# Sheet1TASK1.net
KiCad netlist of a schematic drawn in Altium Designer
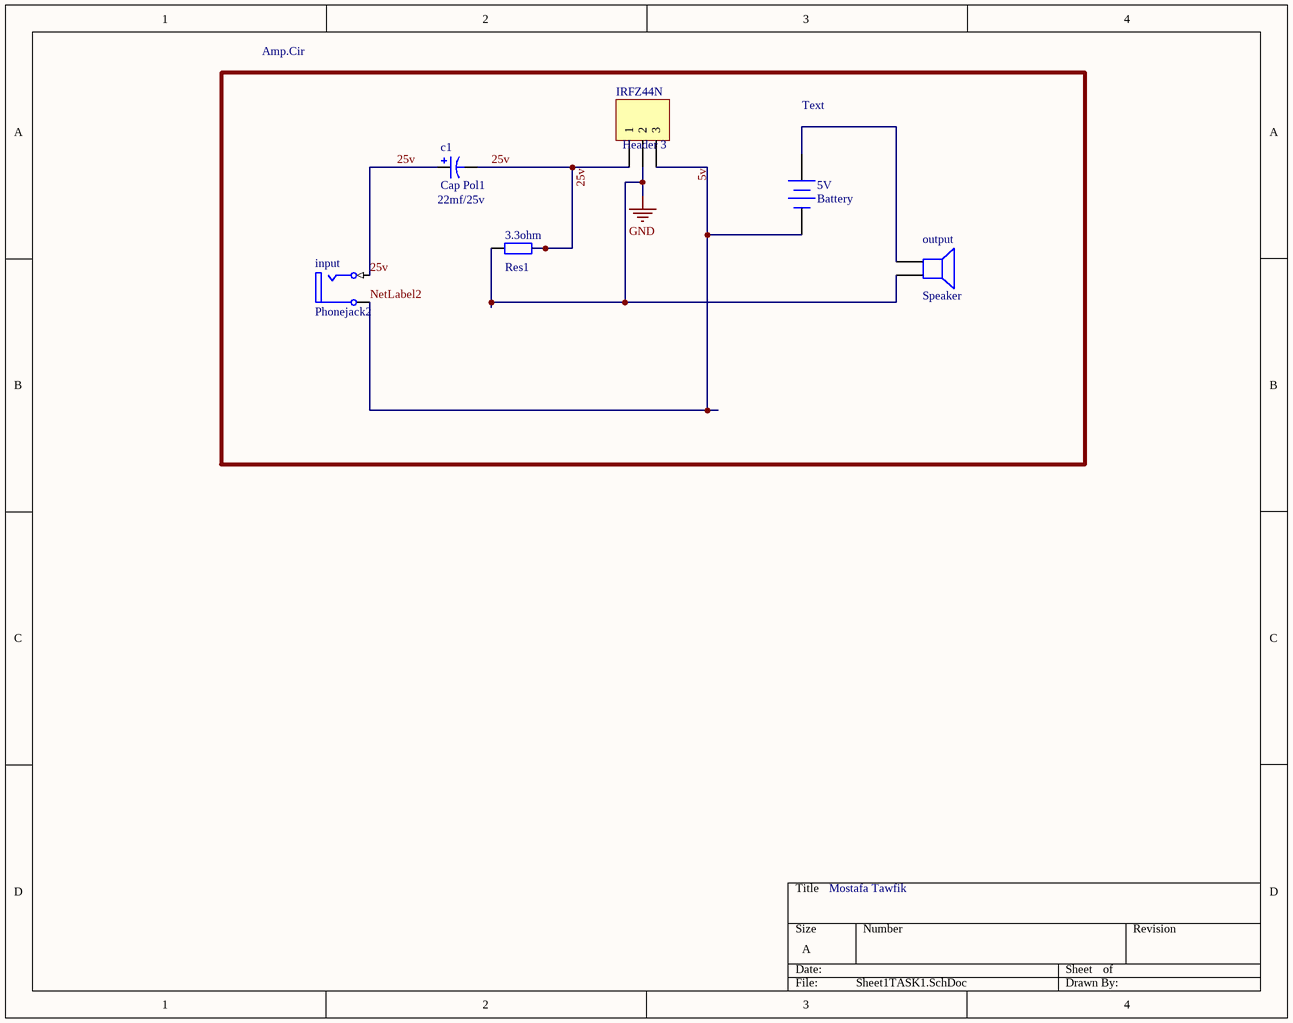
[diagram p0: Sheet1TASK1.SchDoc]

(export (version "E")
  (design (tool "Eeschema 10.0.6"))
  (components
    (comp (ref "3.3ohm")
      (value "Res1")
      (footprint "AXIAL-0.4")
      (description "Resistor")
      (fields (field (name "PUBLISHER") "Altium Limited"))
      (libsource (lib "Miscellaneous Devices") (part "Res2"))
    )
    (comp (ref "5V")
      (value "Battery")
      (footprint "BAT-2")
      (description "Multicell Battery")
      (fields (field (name "PUBLISHER") "Altium Limited"))
      (libsource (lib "Miscellaneous Devices") (part "Battery"))
    )
    (comp (ref "c1")
      (value "Cap Pol1")
      (footprint "RB7.6-15")
      (description "Polarized Capacitor (Radial)")
      (fields (field (name "ALTIUM_VALUE") "22mf/25v") (field (name "PUBLISHER") "Altium Limited"))
      (libsource (lib "Miscellaneous Devices") (part "Cap Pol1"))
    )
    (comp (ref "input")
      (value "Phonejack2")
      (footprint "JACK/6-V2")
      (description "Jack Socket, 1/4\" [6.5mm], Thru-Hole, Vertical, 2-Conductor Open Circuit")
      (fields (field (name "PUBLISHER") "Altium Limited"))
      (libsource (lib "Miscellaneous Connectors") (part "Phonejack2"))
    )
    (comp (ref "IRFZ44N")
      (value "Header 3")
      (footprint "HDR1X3")
      (description "Header, 3-Pin")
      (fields (field (name "PUBLISHER") "Altium Limited"))
      (libsource (lib "Miscellaneous Connectors") (part "Header 3"))
    )
    (comp (ref "output")
      (value "Speaker")
      (footprint "PIN2")
      (description "Loudspeaker")
      (fields (field (name "PUBLISHER") "Altium Limited"))
      (libsource (lib "Miscellaneous Devices") (part "Speaker"))
    )
  )
  (nets
    (net (code "1") (name "/5v") (class "Default")
      (node (ref "5V") (pin "2") (pinfunction "-_2") (pintype "passive"))
      (node (ref "IRFZ44N") (pin "3") (pinfunction "3_3") (pintype "passive"))
      (node (ref "input") (pin "5") (pinfunction "S_5") (pintype "power_in"))
    )
    (net (code "2") (name "/25v") (class "Default")
      (node (ref "3.3ohm") (pin "2") (pinfunction "2_2") (pintype "passive"))
      (node (ref "IRFZ44N") (pin "1") (pinfunction "1_1") (pintype "passive"))
      (node (ref "c1") (pin "1") (pinfunction "1_1") (pintype "passive"))
      (node (ref "c1") (pin "2") (pinfunction "2_2") (pintype "passive"))
      (node (ref "input") (pin "1") (pinfunction "T_1") (pintype "input"))
    )
    (net (code "3") (name "GND") (class "Default")
      (node (ref "3.3ohm") (pin "1") (pinfunction "1_1") (pintype "passive"))
      (node (ref "IRFZ44N") (pin "2") (pinfunction "2_2") (pintype "passive"))
      (node (ref "output") (pin "2") (pinfunction "2_2") (pintype "passive"))
    )
    (net (code "4") (name "Net-(5V-+)") (class "Default")
      (node (ref "5V") (pin "1") (pinfunction "+_1") (pintype "passive"))
      (node (ref "output") (pin "1") (pinfunction "1_1") (pintype "passive"))
    )
  )
)
